# MAX3232.net
KiCad netlist of a schematic drawn in Altium Designer
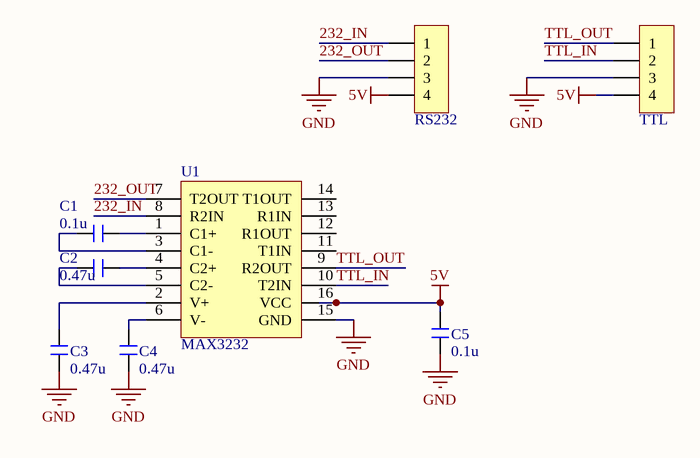
[diagram p0: MAX3232.SchDoc]

(export (version "E")
  (design (tool "Eeschema 10.0.6"))
  (components
    (comp (ref "C1")
      (value "0.1u")
      (footprint "C 0603_L")
      (description "贴片电容")
      (libsource (lib "01 - 电容-电阻-电感") (part "C"))
    )
    (comp (ref "C2")
      (value "0.47u")
      (footprint "C 0603_L")
      (description "贴片电容")
      (libsource (lib "01 - 电容-电阻-电感") (part "C"))
    )
    (comp (ref "C3")
      (value "0.47u")
      (footprint "C 0603_L")
      (description "贴片电容")
      (libsource (lib "01 - 电容-电阻-电感") (part "C"))
    )
    (comp (ref "C4")
      (value "0.47u")
      (footprint "C 0603_L")
      (description "贴片电容")
      (libsource (lib "01 - 电容-电阻-电感") (part "C"))
    )
    (comp (ref "C5")
      (value "0.1u")
      (footprint "C 0603_L")
      (description "贴片电容")
      (libsource (lib "01 - 电容-电阻-电感") (part "C"))
    )
    (comp (ref "RS232")
      (value "HDR-1X4")
      (footprint "XH2.54-WI-4P")
      (description "4P接插件")
      (libsource (lib "18 - 接插件-脚距2.54mm (100mil) ") (part "Header 4"))
    )
    (comp (ref "TTL")
      (value "HDR-1X4")
      (footprint "GH1.25-WS-4P")
      (description "4P接插件")
      (libsource (lib "14 - 接插件-脚距1.25mm") (part "Header 4"))
    )
    (comp (ref "U1")
      (value "MAX3232")
      (footprint "SOIC-16")
      (description "通讯IC")
      (libsource (lib "36 - MAX系列芯片") (part "MAX3232"))
    )
  )
  (nets
    (net (code "1") (name "/232_IN") (class "Default")
      (node (ref "RS232") (pin "1") (pinfunction "1_1") (pintype "passive"))
      (node (ref "U1") (pin "8") (pinfunction "R2IN_8") (pintype "passive"))
    )
    (net (code "2") (name "/232_OUT") (class "Default")
      (node (ref "RS232") (pin "2") (pinfunction "2_2") (pintype "passive"))
      (node (ref "U1") (pin "7") (pinfunction "T2OUT_7") (pintype "passive"))
    )
    (net (code "3") (name "/TTL_IN") (class "Default")
      (node (ref "TTL") (pin "2") (pinfunction "2_2") (pintype "passive"))
      (node (ref "U1") (pin "10") (pinfunction "T2IN_10") (pintype "passive"))
    )
    (net (code "4") (name "/TTL_OUT") (class "Default")
      (node (ref "TTL") (pin "1") (pinfunction "1_1") (pintype "passive"))
      (node (ref "U1") (pin "9") (pinfunction "R2OUT_9") (pintype "passive"))
    )
    (net (code "5") (name "5V") (class "Default")
      (node (ref "C5") (pin "2") (pinfunction "2_2") (pintype "passive"))
      (node (ref "RS232") (pin "4") (pinfunction "4_4") (pintype "passive"))
      (node (ref "TTL") (pin "4") (pinfunction "4_4") (pintype "passive"))
      (node (ref "U1") (pin "16") (pinfunction "VCC_16") (pintype "power_in"))
    )
    (net (code "6") (name "GND") (class "Default")
      (node (ref "C3") (pin "1") (pinfunction "1_1") (pintype "passive"))
      (node (ref "C4") (pin "1") (pinfunction "1_1") (pintype "passive"))
      (node (ref "C5") (pin "1") (pinfunction "1_1") (pintype "passive"))
      (node (ref "RS232") (pin "3") (pinfunction "3_3") (pintype "passive"))
      (node (ref "TTL") (pin "3") (pinfunction "3_3") (pintype "passive"))
      (node (ref "U1") (pin "15") (pinfunction "GND_15") (pintype "power_in"))
    )
    (net (code "7") (name "Net-(U1-C1+)") (class "Default")
      (node (ref "C1") (pin "2") (pinfunction "2_2") (pintype "passive"))
      (node (ref "U1") (pin "1") (pinfunction "C1+_1") (pintype "passive"))
    )
    (net (code "8") (name "Net-(U1-C1-)") (class "Default")
      (node (ref "C1") (pin "1") (pinfunction "1_1") (pintype "passive"))
      (node (ref "U1") (pin "3") (pinfunction "C1-_3") (pintype "passive"))
    )
    (net (code "9") (name "Net-(U1-C2+)") (class "Default")
      (node (ref "C2") (pin "2") (pinfunction "2_2") (pintype "passive"))
      (node (ref "U1") (pin "4") (pinfunction "C2+_4") (pintype "passive"))
    )
    (net (code "10") (name "Net-(U1-C2-)") (class "Default")
      (node (ref "C2") (pin "1") (pinfunction "1_1") (pintype "passive"))
      (node (ref "U1") (pin "5") (pinfunction "C2-_5") (pintype "passive"))
    )
    (net (code "11") (name "Net-(U1-V+)") (class "Default")
      (node (ref "C3") (pin "2") (pinfunction "2_2") (pintype "passive"))
      (node (ref "U1") (pin "2") (pinfunction "V+_2") (pintype "passive"))
    )
    (net (code "12") (name "Net-(U1-V-)") (class "Default")
      (node (ref "C4") (pin "2") (pinfunction "2_2") (pintype "passive"))
      (node (ref "U1") (pin "6") (pinfunction "V-_6") (pintype "passive"))
    )
    (net (code "13") (name "unconnected-(U1-R1IN-Pad13)") (class "Default")
      (node (ref "U1") (pin "13") (pinfunction "R1IN_13") (pintype "passive"))
    )
    (net (code "14") (name "unconnected-(U1-R1OUT-Pad12)") (class "Default")
      (node (ref "U1") (pin "12") (pinfunction "R1OUT_12") (pintype "passive"))
    )
    (net (code "15") (name "unconnected-(U1-T1IN-Pad11)") (class "Default")
      (node (ref "U1") (pin "11") (pinfunction "T1IN_11") (pintype "passive"))
    )
    (net (code "16") (name "unconnected-(U1-T1OUT-Pad14)") (class "Default")
      (node (ref "U1") (pin "14") (pinfunction "T1OUT_14") (pintype "passive"))
    )
  )
)
